# Carriage_Minifit_PCB.net
KiCad netlist of a schematic drawn in EAGLE
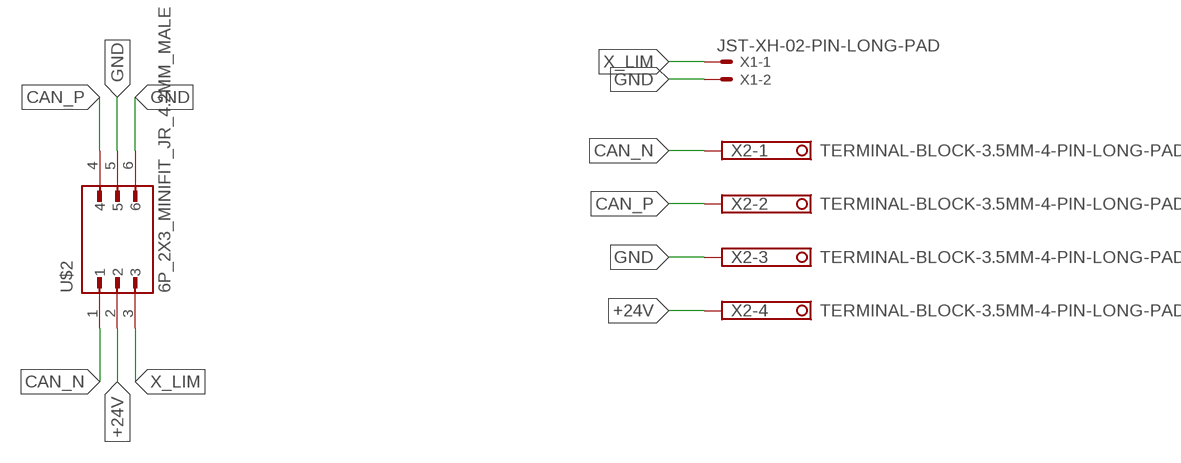
[diagram p0: schematic, sheet 1]

(export (version "E")
  (design (tool "Eeschema 10.0.6"))
  (components
    (comp (ref "U$2")
      (value "6P_2X3_MINIFIT_JR_4.2MM_MALE")
      (footprint "eagle-import:6P_2X3_MINIFIT_JR_4.2MM_MALE")
      (libsource (lib "eagle-import") (part "6P_2X3_MINIFIT_JR_4.2MM_MALE"))
    )
    (comp (ref "X1")
      (value "JST-XH-02-PIN-LONG-PAD")
      (footprint "eagle-import:JST-XH-02-PACKAGE-LONG-PAD")
      (libsource (lib "eagle-import") (part "JST-XH-02-PIN-LONG-PAD"))
    )
    (comp (ref "X2")
      (value "TERMINAL-BLOCK-3.5MM-4-PIN-LONG-PAD")
      (footprint "eagle-import:TERMINAL-BLOCK-4-PIN-3.5MM-LONG-PAD")
      (libsource (lib "eagle-import") (part "TERMINAL-BLOCK-3.5MM-4-PIN-LONG-PAD"))
    )
  )
  (nets
    (net (code "1") (name "+24V") (class "Default")
      (node (ref "U$2") (pin "2") (pinfunction "2_2") (pintype "passive"))
      (node (ref "X2") (pin "4") (pinfunction "K_4") (pintype "passive"))
    )
    (net (code "2") (name "CAN_N") (class "Default")
      (node (ref "U$2") (pin "1") (pinfunction "1_1") (pintype "passive"))
      (node (ref "X2") (pin "1") (pinfunction "K_1") (pintype "passive"))
    )
    (net (code "3") (name "CAN_P") (class "Default")
      (node (ref "U$2") (pin "4") (pinfunction "4_4") (pintype "passive"))
      (node (ref "X2") (pin "2") (pinfunction "K_2") (pintype "passive"))
    )
    (net (code "4") (name "GND") (class "Default")
      (node (ref "U$2") (pin "5") (pinfunction "5_5") (pintype "passive"))
      (node (ref "U$2") (pin "6") (pinfunction "6_6") (pintype "passive"))
      (node (ref "X1") (pin "2") (pinfunction "S_2") (pintype "passive"))
      (node (ref "X2") (pin "3") (pinfunction "K_3") (pintype "passive"))
    )
    (net (code "5") (name "X_LIM") (class "Default")
      (node (ref "U$2") (pin "3") (pinfunction "3_3") (pintype "passive"))
      (node (ref "X1") (pin "1") (pinfunction "S_1") (pintype "passive"))
    )
  )
)
